# Jds-040-Usb-C-Single-Leds.net
KiCad netlist of a schematic drawn in EAGLE
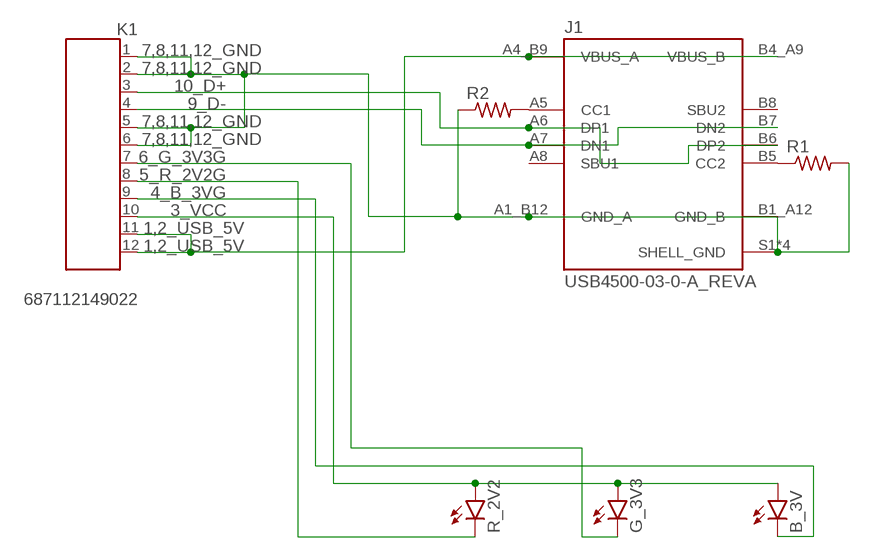
[diagram p0: schematic, sheet 1]

(export (version "E")
  (design (tool "Eeschema 10.0.6"))
  (components
    (comp (ref "B_3V")
      (value "BEAGLEBONE_BLUE_LED0603")
      (footprint "eagle-import:BEAGLEBONE_BLUE_BEAGLEBONE_BLUE_LED-0603")
      (libsource (lib "eagle-import") (part "BEAGLEBONE_BLUE_LED0603"))
    )
    (comp (ref "G_3V3")
      (value "BEAGLEBONE_BLUE_LED0603")
      (footprint "eagle-import:BEAGLEBONE_BLUE_BEAGLEBONE_BLUE_LED-0603")
      (libsource (lib "eagle-import") (part "BEAGLEBONE_BLUE_LED0603"))
    )
    (comp (ref "J1")
      (value "USB4500-03-0-A_REVA")
      (footprint "eagle-import:GCT_USB4500-03-0-A_REVA")
      (fields (field (name "MF") "Global Connector Technology") (field (name "MP") "USB4500-03-0-A"))
      (libsource (lib "eagle-import") (part "USB4500-03-0-A_REVA"))
    )
    (comp (ref "K1")
      (value "687112149022")
      (footprint "eagle-import:687112149022")
      (libsource (lib "eagle-import") (part "687112149022"))
    )
    (comp (ref "R1")
      (value "5k1")
      (footprint "eagle-import:RES_0603")
      (fields
        (field (name "DIGIKEY_PART_NUMBER") "311-0.0GRTR-ND")
        (field (name "MANUFACTURER") "Yageo")
        (field (name "MPN") "RC0603JR-070RL")
        (field (name "CREATED_BY") "PCBLayout.com")
      )
      (libsource (lib "eagle-import") (part "RC0603JR-070RL"))
    )
    (comp (ref "R2")
      (value "5k1")
      (footprint "eagle-import:RES_0603")
      (fields
        (field (name "DIGIKEY_PART_NUMBER") "311-0.0GRTR-ND")
        (field (name "MANUFACTURER") "Yageo")
        (field (name "MPN") "RC0603JR-070RL")
        (field (name "CREATED_BY") "PCBLayout.com")
      )
      (libsource (lib "eagle-import") (part "RC0603JR-070RL"))
    )
    (comp (ref "R_2V2")
      (value "BEAGLEBONE_BLUE_LED0603")
      (footprint "eagle-import:BEAGLEBONE_BLUE_BEAGLEBONE_BLUE_LED-0603")
      (libsource (lib "eagle-import") (part "BEAGLEBONE_BLUE_LED0603"))
    )
  )
  (nets
    (net (code "1") (name "/1,2_USB_5V") (class "Default")
      (node (ref "J1") (pin "A4_B9") (pinfunction "VBUS_A_A4_B9") (pintype "power_in"))
      (node (ref "J1") (pin "B4_A9") (pinfunction "VBUS_B_B4_A9") (pintype "power_in"))
      (node (ref "K1") (pin "11") (pinfunction "11_11") (pintype "passive"))
      (node (ref "K1") (pin "12") (pinfunction "12_12") (pintype "passive"))
    )
    (net (code "2") (name "/3_VCC") (class "Default")
      (node (ref "B_3V") (pin "A") (pinfunction "A_A") (pintype "passive"))
      (node (ref "G_3V3") (pin "A") (pinfunction "A_A") (pintype "passive"))
      (node (ref "K1") (pin "10") (pinfunction "10_10") (pintype "passive"))
      (node (ref "R_2V2") (pin "A") (pinfunction "A_A") (pintype "passive"))
    )
    (net (code "3") (name "/4_B_3VG") (class "Default")
      (node (ref "B_3V") (pin "C") (pinfunction "C_C") (pintype "passive"))
      (node (ref "K1") (pin "9") (pinfunction "9_9") (pintype "passive"))
    )
    (net (code "4") (name "/5_R_2V2G") (class "Default")
      (node (ref "K1") (pin "8") (pinfunction "8_8") (pintype "passive"))
      (node (ref "R_2V2") (pin "C") (pinfunction "C_C") (pintype "passive"))
    )
    (net (code "5") (name "/6_G_3V3G") (class "Default")
      (node (ref "G_3V3") (pin "C") (pinfunction "C_C") (pintype "passive"))
      (node (ref "K1") (pin "7") (pinfunction "7_7") (pintype "passive"))
    )
    (net (code "6") (name "/7,8,11,12_GND") (class "Default")
      (node (ref "J1") (pin "A1_B12") (pinfunction "GND_A_A1_B12") (pintype "power_in"))
      (node (ref "J1") (pin "B1_A12") (pinfunction "GND_B_B1_A12") (pintype "power_in"))
      (node (ref "J1") (pin "S1") (pinfunction "SHELL_GND_S1") (pintype "power_in"))
      (node (ref "J1") (pin "S2") (pinfunction "SHELL_GND_S2") (pintype "power_in"))
      (node (ref "J1") (pin "S3") (pinfunction "SHELL_GND_S3") (pintype "power_in"))
      (node (ref "J1") (pin "S4") (pinfunction "SHELL_GND_S4") (pintype "power_in"))
      (node (ref "K1") (pin "1") (pinfunction "1_1") (pintype "passive"))
      (node (ref "K1") (pin "2") (pinfunction "2_2") (pintype "passive"))
      (node (ref "K1") (pin "5") (pinfunction "5_5") (pintype "passive"))
      (node (ref "K1") (pin "6") (pinfunction "6_6") (pintype "passive"))
      (node (ref "R1") (pin "2") (pinfunction "2_2") (pintype "passive"))
      (node (ref "R2") (pin "1") (pinfunction "1_1") (pintype "passive"))
    )
    (net (code "7") (name "/9_D-") (class "Default")
      (node (ref "J1") (pin "A7") (pinfunction "DN1_A7") (pintype "bidirectional"))
      (node (ref "J1") (pin "B7") (pinfunction "DN2_B7") (pintype "bidirectional"))
      (node (ref "K1") (pin "4") (pinfunction "4_4") (pintype "passive"))
    )
    (net (code "8") (name "/10_D+") (class "Default")
      (node (ref "J1") (pin "A6") (pinfunction "DP1_A6") (pintype "bidirectional"))
      (node (ref "J1") (pin "B6") (pinfunction "DP2_B6") (pintype "bidirectional"))
      (node (ref "K1") (pin "3") (pinfunction "3_3") (pintype "passive"))
    )
    (net (code "9") (name "Net-(J1-CC1)") (class "Default")
      (node (ref "J1") (pin "A5") (pinfunction "CC1_A5") (pintype "bidirectional"))
      (node (ref "R2") (pin "2") (pinfunction "2_2") (pintype "passive"))
    )
    (net (code "10") (name "Net-(J1-CC2)") (class "Default")
      (node (ref "J1") (pin "B5") (pinfunction "CC2_B5") (pintype "bidirectional"))
      (node (ref "R1") (pin "1") (pinfunction "1_1") (pintype "passive"))
    )
    (net (code "11") (name "unconnected-(J1-SBU1-PadA8)") (class "Default")
      (node (ref "J1") (pin "A8") (pinfunction "SBU1_A8") (pintype "bidirectional"))
    )
    (net (code "12") (name "unconnected-(J1-SBU2-PadB8)") (class "Default")
      (node (ref "J1") (pin "B8") (pinfunction "SBU2_B8") (pintype "bidirectional"))
    )
  )
)
